# P82B96-I2c-Bus-Extender-V004.net
KiCad netlist of a schematic drawn in EAGLE
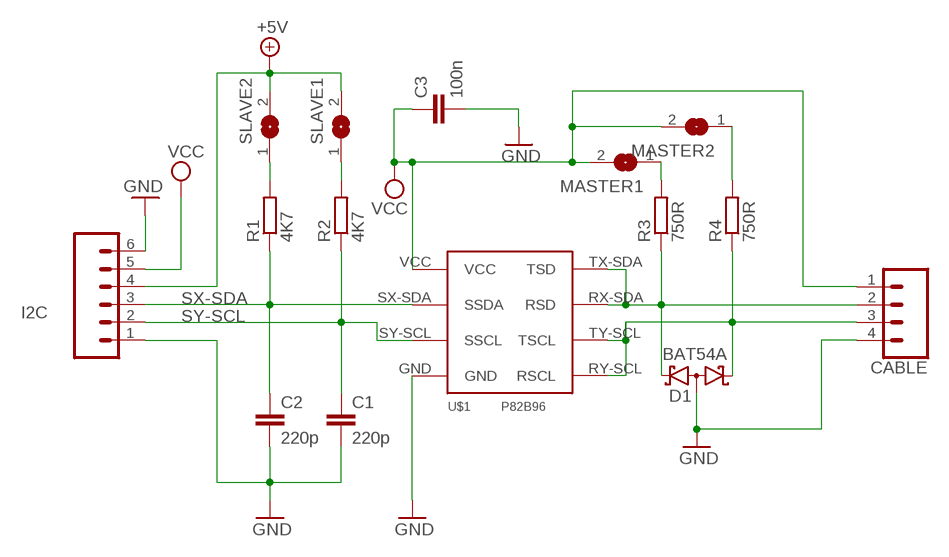
[diagram p0: schematic, sheet 1]

(export (version "E")
  (design (tool "Eeschema 10.0.6"))
  (components
    (comp (ref "C1")
      (value "220p")
      (footprint "eagle-import:C0805K")
      (libsource (lib "eagle-import") (part "C-EUC0805K"))
    )
    (comp (ref "C2")
      (value "220p")
      (footprint "eagle-import:C0805K")
      (libsource (lib "eagle-import") (part "C-EUC0805K"))
    )
    (comp (ref "C3")
      (value "100n")
      (footprint "eagle-import:C0805K")
      (libsource (lib "eagle-import") (part "C-EUC0805K"))
    )
    (comp (ref "CABLE")
      (value "CONN_04LOCK_LONGPADS")
      (footprint "eagle-import:1X04_LOCK_LONGPADS")
      (libsource (lib "eagle-import") (part "CONN_04LOCK_LONGPADS"))
    )
    (comp (ref "D1")
      (value "BAT54A")
      (footprint "eagle-import:SOT23")
      (libsource (lib "eagle-import") (part "BAT54A"))
    )
    (comp (ref "I2C")
      (value "CONN_06LONGPADS")
      (footprint "eagle-import:1X06_LONGPADS")
      (libsource (lib "eagle-import") (part "CONN_06LONGPADS"))
    )
    (comp (ref "MASTER1")
      (value "SJ")
      (footprint "eagle-import:SJ")
      (libsource (lib "eagle-import") (part "SJ"))
    )
    (comp (ref "MASTER2")
      (value "SJ")
      (footprint "eagle-import:SJ")
      (libsource (lib "eagle-import") (part "SJ"))
    )
    (comp (ref "R1")
      (value "4K7")
      (footprint "eagle-import:R0805W")
      (libsource (lib "eagle-import") (part "R-EU_R0805W"))
    )
    (comp (ref "R2")
      (value "4K7")
      (footprint "eagle-import:R0805W")
      (libsource (lib "eagle-import") (part "R-EU_R0805W"))
    )
    (comp (ref "R3")
      (value "750R")
      (footprint "eagle-import:R0805W")
      (libsource (lib "eagle-import") (part "R-EU_R0805W"))
    )
    (comp (ref "R4")
      (value "750R")
      (footprint "eagle-import:R0805W")
      (libsource (lib "eagle-import") (part "R-EU_R0805W"))
    )
    (comp (ref "SLAVE1")
      (value "SJ")
      (footprint "eagle-import:SJ")
      (libsource (lib "eagle-import") (part "SJ"))
    )
    (comp (ref "SLAVE2")
      (value "SJ")
      (footprint "eagle-import:SJ")
      (libsource (lib "eagle-import") (part "SJ"))
    )
    (comp (ref "U$1")
      (value "P82B96-NEW")
      (footprint "eagle-import:SOIC8")
      (libsource (lib "eagle-import") (part "P82B96-NEW"))
    )
  )
  (nets
    (net (code "1") (name "+5V") (class "Default")
      (node (ref "I2C") (pin "4") (pinfunction "4_4") (pintype "passive"))
      (node (ref "SLAVE1") (pin "2") (pinfunction "2_2") (pintype "passive"))
      (node (ref "SLAVE2") (pin "2") (pinfunction "2_2") (pintype "passive"))
    )
    (net (code "2") (name "/SX-SDA") (class "Default")
      (node (ref "C2") (pin "1") (pinfunction "1_1") (pintype "passive"))
      (node (ref "I2C") (pin "3") (pinfunction "3_3") (pintype "passive"))
      (node (ref "R1") (pin "1") (pinfunction "1_1") (pintype "passive"))
      (node (ref "U$1") (pin "SX-SDA") (pinfunction "SSDA_SX-SDA") (pintype "bidirectional"))
    )
    (net (code "3") (name "/SY-SCL") (class "Default")
      (node (ref "C1") (pin "1") (pinfunction "1_1") (pintype "passive"))
      (node (ref "I2C") (pin "2") (pinfunction "2_2") (pintype "passive"))
      (node (ref "R2") (pin "1") (pinfunction "1_1") (pintype "passive"))
      (node (ref "U$1") (pin "SY-SCL") (pinfunction "SSCL_SY-SCL") (pintype "bidirectional"))
    )
    (net (code "4") (name "GND") (class "Default")
      (node (ref "C1") (pin "2") (pinfunction "2_2") (pintype "passive"))
      (node (ref "C2") (pin "2") (pinfunction "2_2") (pintype "passive"))
      (node (ref "C3") (pin "2") (pinfunction "2_2") (pintype "passive"))
      (node (ref "CABLE") (pin "4") (pinfunction "4_4") (pintype "passive"))
      (node (ref "D1") (pin "3") (pinfunction "AA_3") (pintype "passive"))
      (node (ref "I2C") (pin "1") (pinfunction "1_1") (pintype "passive"))
      (node (ref "I2C") (pin "6") (pinfunction "6_6") (pintype "passive"))
      (node (ref "U$1") (pin "GND") (pinfunction "GND_GND") (pintype "bidirectional"))
    )
    (net (code "5") (name "Net-(D1-K1)") (class "Default")
      (node (ref "CABLE") (pin "3") (pinfunction "3_3") (pintype "passive"))
      (node (ref "D1") (pin "1") (pinfunction "K1_1") (pintype "passive"))
      (node (ref "R4") (pin "1") (pinfunction "1_1") (pintype "passive"))
      (node (ref "U$1") (pin "RY-SCL") (pinfunction "RSCL_RY-SCL") (pintype "bidirectional"))
      (node (ref "U$1") (pin "TY-SCL") (pinfunction "TSCL_TY-SCL") (pintype "bidirectional"))
    )
    (net (code "6") (name "Net-(D1-K2)") (class "Default")
      (node (ref "CABLE") (pin "2") (pinfunction "2_2") (pintype "passive"))
      (node (ref "D1") (pin "2") (pinfunction "K2_2") (pintype "passive"))
      (node (ref "R3") (pin "1") (pinfunction "1_1") (pintype "passive"))
      (node (ref "U$1") (pin "RX-SDA") (pinfunction "RSD_RX-SDA") (pintype "bidirectional"))
      (node (ref "U$1") (pin "TX-SDA") (pinfunction "TSD_TX-SDA") (pintype "bidirectional"))
    )
    (net (code "7") (name "Net-(MASTER1-Pad1)") (class "Default")
      (node (ref "MASTER1") (pin "1") (pinfunction "1_1") (pintype "passive"))
      (node (ref "R3") (pin "2") (pinfunction "2_2") (pintype "passive"))
    )
    (net (code "8") (name "Net-(MASTER2-Pad1)") (class "Default")
      (node (ref "MASTER2") (pin "1") (pinfunction "1_1") (pintype "passive"))
      (node (ref "R4") (pin "2") (pinfunction "2_2") (pintype "passive"))
    )
    (net (code "9") (name "Net-(R1-Pad2)") (class "Default")
      (node (ref "R1") (pin "2") (pinfunction "2_2") (pintype "passive"))
      (node (ref "SLAVE2") (pin "1") (pinfunction "1_1") (pintype "passive"))
    )
    (net (code "10") (name "Net-(R2-Pad2)") (class "Default")
      (node (ref "R2") (pin "2") (pinfunction "2_2") (pintype "passive"))
      (node (ref "SLAVE1") (pin "1") (pinfunction "1_1") (pintype "passive"))
    )
    (net (code "11") (name "VCC") (class "Default")
      (node (ref "C3") (pin "1") (pinfunction "1_1") (pintype "passive"))
      (node (ref "CABLE") (pin "1") (pinfunction "1_1") (pintype "passive"))
      (node (ref "I2C") (pin "5") (pinfunction "5_5") (pintype "passive"))
      (node (ref "MASTER1") (pin "2") (pinfunction "2_2") (pintype "passive"))
      (node (ref "MASTER2") (pin "2") (pinfunction "2_2") (pintype "passive"))
      (node (ref "U$1") (pin "VCC") (pinfunction "VCC_VCC") (pintype "bidirectional"))
    )
  )
)
